# USBPowerv1_0.net
KiCad netlist of a schematic drawn in Altium Designer
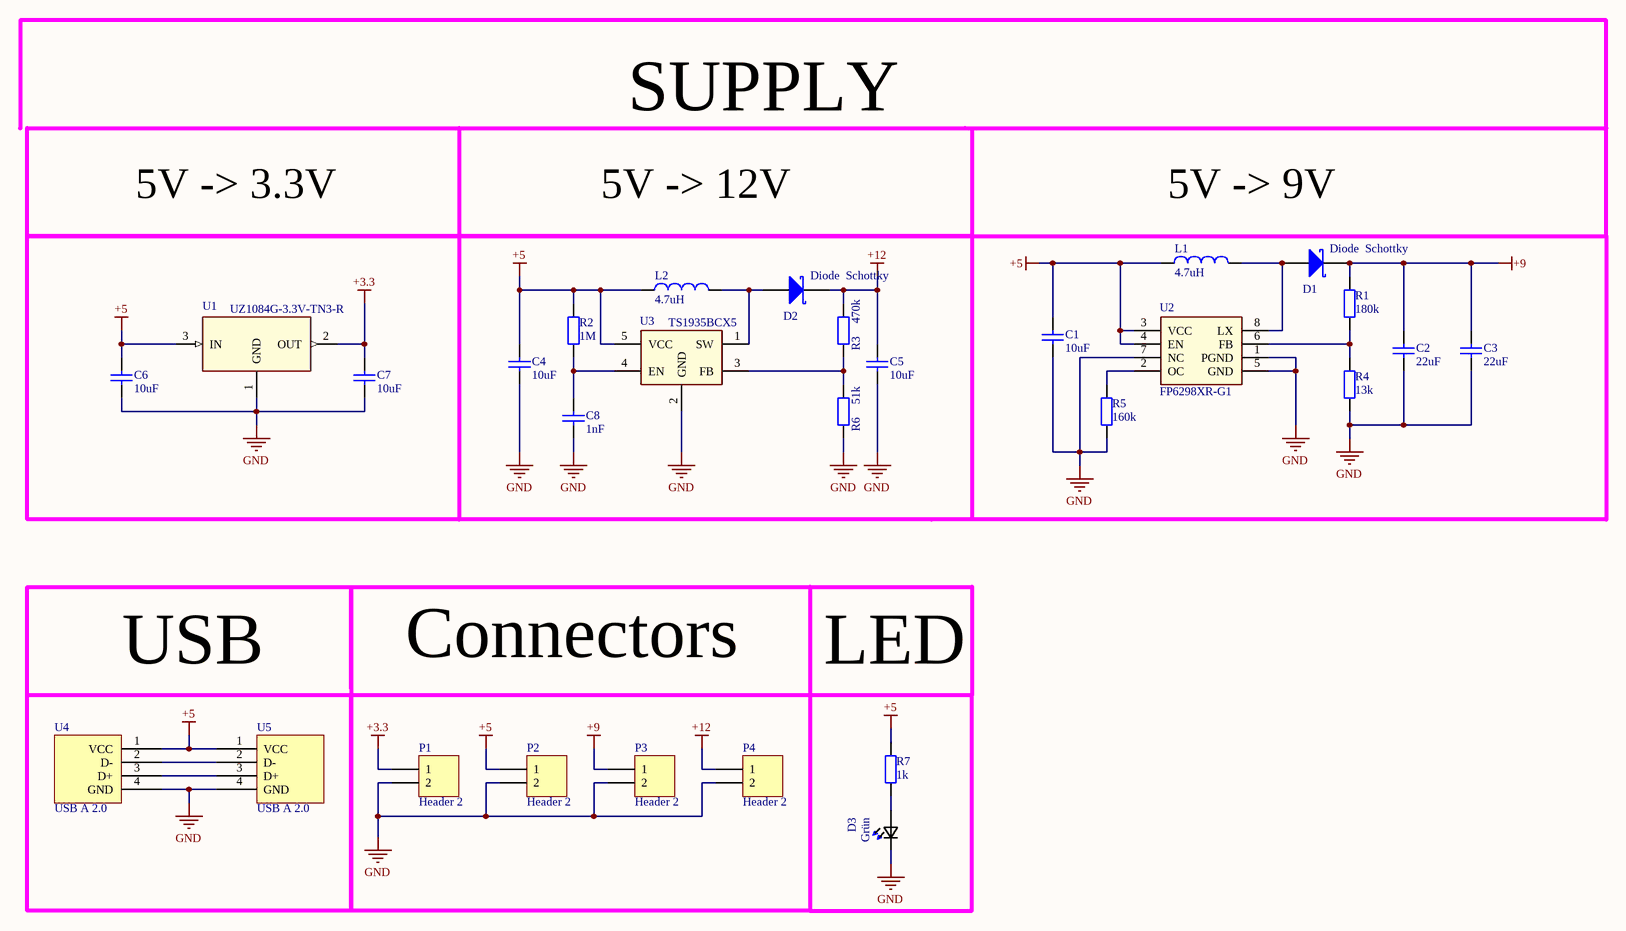
[diagram p0: USBPowerv1.0.SchDoc]

(export (version "E")
  (design (tool "Eeschema 10.0.6"))
  (components
    (comp (ref "C1")
      (value "10uF")
      (footprint "CAP_0603i_1608m -L")
      (description "capacitor")
      (libsource (lib "IDSC std generic parts") (part "Cap"))
    )
    (comp (ref "C2")
      (value "22uF")
      (footprint "CAP_0805i_2012m -N")
      (description "capacitor")
      (libsource (lib "IDSC std generic parts") (part "Cap"))
    )
    (comp (ref "C3")
      (value "22uF")
      (footprint "CAP_0805i_2012m -N")
      (description "capacitor")
      (libsource (lib "IDSC std generic parts") (part "Cap"))
    )
    (comp (ref "C4")
      (value "10uF")
      (footprint "CAP_0603i_1608m -L")
      (description "capacitor")
      (libsource (lib "IDSC std generic parts") (part "Cap"))
    )
    (comp (ref "C5")
      (value "10uF")
      (footprint "CAP_0603i_1608m -L")
      (description "capacitor")
      (libsource (lib "IDSC std generic parts") (part "Cap"))
    )
    (comp (ref "C6")
      (value "10uF")
      (footprint "CAP_0603i_1608m -L")
      (description "capacitor")
      (libsource (lib "IDSC std generic parts") (part "Cap"))
    )
    (comp (ref "C7")
      (value "10uF")
      (footprint "CAP_0603i_1608m -L")
      (description "capacitor")
      (libsource (lib "IDSC std generic parts") (part "Cap"))
    )
    (comp (ref "C8")
      (value "1nF")
      (footprint "CAP_0402i_1005m -N")
      (description "capacitor")
      (libsource (lib "IDSC std generic parts") (part "Cap"))
    )
    (comp (ref "D1")
      (value "Diode  Schottky")
      (footprint "SOD123")
      (description "Schottky Diode")
      (libsource (lib "IDSC std generic parts") (part "Diode  Schottky"))
    )
    (comp (ref "D2")
      (value "Diode  Schottky")
      (footprint "SOD123")
      (description "Schottky Diode")
      (libsource (lib "IDSC std generic parts") (part "Diode  Schottky"))
    )
    (comp (ref "D3")
      (value "Grün")
      (footprint "*0603")
      (description "LED; SMD; 0603; gr黱; 35mcd; 1.6x0.8x0.55mm; 130掳; 2梅2.V; 20mA")
      (fields (field (name "MP") "LTST-C191KGKT") (field (name "DIGI-KEY_PART_NUMBER") "160-1446-1-ND"))
      (libsource (lib "Funk") (part "LTST-C191KGKT"))
    )
    (comp (ref "L1")
      (value "4.7uH")
      (footprint "IND_0603i_1608m -L")
      (description "Inductor")
      (libsource (lib "IDSC std generic parts") (part "Inductor"))
    )
    (comp (ref "L2")
      (value "4.7uH")
      (footprint "IND_0603i_1608m -L")
      (description "Inductor")
      (libsource (lib "IDSC std generic parts") (part "Inductor"))
    )
    (comp (ref "P1")
      (value "Header 2")
      (footprint "3.81mm HDR1X2")
      (description "Header, 2-Pin")
      (libsource (lib "IDSC std connectors") (part "Header 2"))
    )
    (comp (ref "P2")
      (value "Header 2")
      (footprint "3.81mm HDR1X2")
      (description "Header, 2-Pin")
      (libsource (lib "IDSC std connectors") (part "Header 2"))
    )
    (comp (ref "P3")
      (value "Header 2")
      (footprint "3.81mm HDR1X2")
      (description "Header, 2-Pin")
      (libsource (lib "IDSC std connectors") (part "Header 2"))
    )
    (comp (ref "P4")
      (value "Header 2")
      (footprint "3.81mm HDR1X2")
      (description "Header, 2-Pin")
      (libsource (lib "IDSC std connectors") (part "Header 2"))
    )
    (comp (ref "R1")
      (value "180k")
      (footprint "RES_0603_1608m -L")
      (description "Resistor")
      (libsource (lib "") (part "Res_2"))
    )
    (comp (ref "R2")
      (value "1M")
      (footprint "RES_0603i_1608m -N")
      (libsource (lib "IDSC std generic parts") (part "Res"))
    )
    (comp (ref "R3")
      (value "470k")
      (footprint "RES_0603i_1608m -N")
      (libsource (lib "IDSC std generic parts") (part "Res"))
    )
    (comp (ref "R4")
      (value "13k")
      (footprint "RES_0603_1608m -L")
      (description "Resistor")
      (libsource (lib "") (part "Res_2"))
    )
    (comp (ref "R5")
      (value "160k")
      (footprint "RES_0603_1608m -L")
      (description "Resistor")
      (libsource (lib "") (part "Res_2"))
    )
    (comp (ref "R6")
      (value "51k")
      (footprint "RES_0603i_1608m -N")
      (libsource (lib "IDSC std generic parts") (part "Res"))
    )
    (comp (ref "R7")
      (value "1k")
      (footprint "RES_0603i_1608m -N")
      (description "Resistor")
      (libsource (lib "") (part "Res_1"))
    )
    (comp (ref "U1")
      (value "UZ1084G-3.3V-TN3-R")
      (footprint "TO-252-2")
      (description "LINEAR VOLTAGE REGULATORS TO-252-2(DPAK) ROHS")
      (fields (field (name "MF") "Diodes Inc.") (field (name "MP") "AZ1117D-3.3TRE1"))
      (libsource (lib "BMA_lib") (part "UZ1084G-3.3V-TN3-R"))
    )
    (comp (ref "U2")
      (value "FP6298XR-G1")
      (footprint "SOP8")
      (libsource (lib "BMA_lib") (part "FP6298XR-G1"))
    )
    (comp (ref "U3")
      (value "TS1935BCX5")
      (footprint "*SOT95P285X145-5N")
      (description "TS1935BCX5 Boost-Schaltregler Adj 1,9A 2,6-5,5Vi SOT23-5")
      (libsource (lib "BMA_lib") (part "TS1935BCX5"))
    )
    (comp (ref "U4")
      (value "USB A 2.0")
      (footprint "USB A 2.0 Male")
      (libsource (lib "LIB") (part "USB A 2.0"))
    )
    (comp (ref "U5")
      (value "USB A 2.0")
      (footprint "OST_USB-A1HSW6")
      (libsource (lib "") (part "USB A 2.0_1"))
    )
  )
  (nets
    (net (code "1") (name "+3.3") (class "Default")
      (node (ref "C7") (pin "2") (pinfunction "2_2") (pintype "passive"))
      (node (ref "P1") (pin "1") (pinfunction "1_1") (pintype "passive"))
      (node (ref "U1") (pin "2") (pinfunction "OUT_2") (pintype "output"))
    )
    (net (code "2") (name "+5") (class "Default")
      (node (ref "C1") (pin "2") (pinfunction "2_2") (pintype "passive"))
      (node (ref "C4") (pin "2") (pinfunction "2_2") (pintype "passive"))
      (node (ref "C6") (pin "2") (pinfunction "2_2") (pintype "passive"))
      (node (ref "L1") (pin "1") (pinfunction "1_1") (pintype "passive"))
      (node (ref "L2") (pin "1") (pinfunction "1_1") (pintype "passive"))
      (node (ref "P2") (pin "1") (pinfunction "1_1") (pintype "passive"))
      (node (ref "R2") (pin "1") (pinfunction "1_1") (pintype "passive"))
      (node (ref "R7") (pin "2") (pinfunction "2_2") (pintype "passive"))
      (node (ref "U1") (pin "3") (pinfunction "IN_3") (pintype "input"))
      (node (ref "U2") (pin "3") (pinfunction "VCC_3") (pintype "passive"))
      (node (ref "U2") (pin "4") (pinfunction "EN_4") (pintype "passive"))
      (node (ref "U3") (pin "5") (pinfunction "VCC_5") (pintype "passive"))
      (node (ref "U4") (pin "1") (pinfunction "VCC_1") (pintype "passive"))
      (node (ref "U5") (pin "1") (pinfunction "VCC_1") (pintype "passive"))
    )
    (net (code "3") (name "+9") (class "Default")
      (node (ref "C2") (pin "2") (pinfunction "2_2") (pintype "passive"))
      (node (ref "C3") (pin "2") (pinfunction "2_2") (pintype "passive"))
      (node (ref "D1") (pin "2") (pinfunction "K_2") (pintype "passive"))
      (node (ref "P3") (pin "1") (pinfunction "1_1") (pintype "passive"))
      (node (ref "R1") (pin "2") (pinfunction "2_2") (pintype "passive"))
    )
    (net (code "4") (name "+12") (class "Default")
      (node (ref "C5") (pin "2") (pinfunction "2_2") (pintype "passive"))
      (node (ref "D2") (pin "2") (pinfunction "K_2") (pintype "passive"))
      (node (ref "P4") (pin "1") (pinfunction "1_1") (pintype "passive"))
      (node (ref "R3") (pin "1") (pinfunction "1_1") (pintype "passive"))
    )
    (net (code "5") (name "GND") (class "Default")
      (node (ref "C1") (pin "1") (pinfunction "1_1") (pintype "passive"))
      (node (ref "C2") (pin "1") (pinfunction "1_1") (pintype "passive"))
      (node (ref "C3") (pin "1") (pinfunction "1_1") (pintype "passive"))
      (node (ref "C4") (pin "1") (pinfunction "1_1") (pintype "passive"))
      (node (ref "C5") (pin "1") (pinfunction "1_1") (pintype "passive"))
      (node (ref "C6") (pin "1") (pinfunction "1_1") (pintype "passive"))
      (node (ref "C7") (pin "1") (pinfunction "1_1") (pintype "passive"))
      (node (ref "C8") (pin "1") (pinfunction "1_1") (pintype "passive"))
      (node (ref "D3") (pin "1") (pinfunction "K2_1") (pintype "passive"))
      (node (ref "P1") (pin "2") (pinfunction "2_2") (pintype "passive"))
      (node (ref "P2") (pin "2") (pinfunction "2_2") (pintype "passive"))
      (node (ref "P3") (pin "2") (pinfunction "2_2") (pintype "passive"))
      (node (ref "P4") (pin "2") (pinfunction "2_2") (pintype "passive"))
      (node (ref "R4") (pin "1") (pinfunction "1_1") (pintype "passive"))
      (node (ref "R5") (pin "1") (pinfunction "1_1") (pintype "passive"))
      (node (ref "R6") (pin "2") (pinfunction "2_2") (pintype "passive"))
      (node (ref "U1") (pin "1") (pinfunction "GND_1") (pintype "power_in"))
      (node (ref "U2") (pin "1") (pinfunction "PGND_1") (pintype "passive"))
      (node (ref "U2") (pin "5") (pinfunction "GND_5") (pintype "passive"))
      (node (ref "U2") (pin "7") (pinfunction "NC_7") (pintype "passive"))
      (node (ref "U3") (pin "2") (pinfunction "GND_2") (pintype "passive"))
      (node (ref "U4") (pin "4") (pinfunction "GND_4") (pintype "passive"))
      (node (ref "U5") (pin "4") (pinfunction "GND_4") (pintype "passive"))
    )
    (net (code "6") (name "Net-(D1-A)") (class "Default")
      (node (ref "D1") (pin "1") (pinfunction "A_1") (pintype "passive"))
      (node (ref "L1") (pin "2") (pinfunction "2_2") (pintype "passive"))
      (node (ref "U2") (pin "8") (pinfunction "LX_8") (pintype "passive"))
    )
    (net (code "7") (name "Net-(D2-A)") (class "Default")
      (node (ref "D2") (pin "1") (pinfunction "A_1") (pintype "passive"))
      (node (ref "L2") (pin "2") (pinfunction "2_2") (pintype "passive"))
      (node (ref "U3") (pin "1") (pinfunction "SW_1") (pintype "passive"))
    )
    (net (code "8") (name "Net-(D3-A2)") (class "Default")
      (node (ref "D3") (pin "2") (pinfunction "A2_2") (pintype "passive"))
      (node (ref "R7") (pin "1") (pinfunction "1_1") (pintype "passive"))
    )
    (net (code "9") (name "Net-(U2-FB)") (class "Default")
      (node (ref "R1") (pin "1") (pinfunction "1_1") (pintype "passive"))
      (node (ref "R4") (pin "2") (pinfunction "2_2") (pintype "passive"))
      (node (ref "U2") (pin "6") (pinfunction "FB_6") (pintype "passive"))
    )
    (net (code "10") (name "Net-(U2-OC)") (class "Default")
      (node (ref "R5") (pin "2") (pinfunction "2_2") (pintype "passive"))
      (node (ref "U2") (pin "2") (pinfunction "OC_2") (pintype "passive"))
    )
    (net (code "11") (name "Net-(U3-EN)") (class "Default")
      (node (ref "C8") (pin "2") (pinfunction "2_2") (pintype "passive"))
      (node (ref "R2") (pin "2") (pinfunction "2_2") (pintype "passive"))
      (node (ref "U3") (pin "4") (pinfunction "EN_4") (pintype "passive"))
    )
    (net (code "12") (name "Net-(U3-FB)") (class "Default")
      (node (ref "R3") (pin "2") (pinfunction "2_2") (pintype "passive"))
      (node (ref "R6") (pin "1") (pinfunction "1_1") (pintype "passive"))
      (node (ref "U3") (pin "3") (pinfunction "FB_3") (pintype "passive"))
    )
    (net (code "13") (name "Net-(U4-D+)") (class "Default")
      (node (ref "U4") (pin "3") (pinfunction "D+_3") (pintype "passive"))
      (node (ref "U5") (pin "3") (pinfunction "D+_3") (pintype "passive"))
    )
    (net (code "14") (name "Net-(U4-D-)") (class "Default")
      (node (ref "U4") (pin "2") (pinfunction "D-_2") (pintype "passive"))
      (node (ref "U5") (pin "2") (pinfunction "D-_2") (pintype "passive"))
    )
  )
)
